# 16bit_Banked_Switches.net
KiCad netlist of a schematic drawn in EAGLE
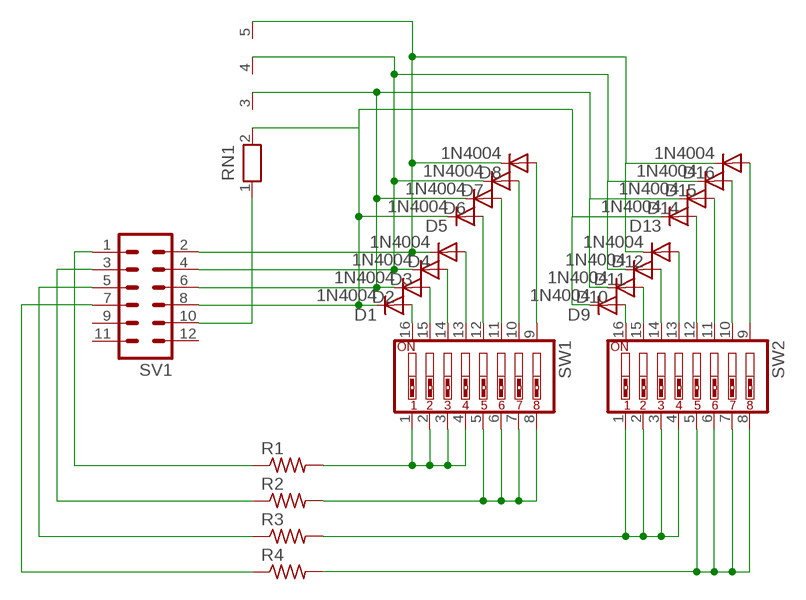
[diagram p0: schematic, sheet 1]

(export (version "E")
  (design (tool "Eeschema 10.0.6"))
  (components
    (comp (ref "D1")
      (value "1N4004")
      (footprint "eagle-import:DO41-10")
      (libsource (lib "eagle-import") (part "1N4004"))
    )
    (comp (ref "D2")
      (value "1N4004")
      (footprint "eagle-import:DO41-10")
      (libsource (lib "eagle-import") (part "1N4004"))
    )
    (comp (ref "D3")
      (value "1N4004")
      (footprint "eagle-import:DO41-10")
      (libsource (lib "eagle-import") (part "1N4004"))
    )
    (comp (ref "D4")
      (value "1N4004")
      (footprint "eagle-import:DO41-10")
      (libsource (lib "eagle-import") (part "1N4004"))
    )
    (comp (ref "D5")
      (value "1N4004")
      (footprint "eagle-import:DO41-10")
      (libsource (lib "eagle-import") (part "1N4004"))
    )
    (comp (ref "D6")
      (value "1N4004")
      (footprint "eagle-import:DO41-10")
      (libsource (lib "eagle-import") (part "1N4004"))
    )
    (comp (ref "D7")
      (value "1N4004")
      (footprint "eagle-import:DO41-10")
      (libsource (lib "eagle-import") (part "1N4004"))
    )
    (comp (ref "D8")
      (value "1N4004")
      (footprint "eagle-import:DO41-10")
      (libsource (lib "eagle-import") (part "1N4004"))
    )
    (comp (ref "D9")
      (value "1N4004")
      (footprint "eagle-import:DO41-10")
      (libsource (lib "eagle-import") (part "1N4004"))
    )
    (comp (ref "D10")
      (value "1N4004")
      (footprint "eagle-import:DO41-10")
      (libsource (lib "eagle-import") (part "1N4004"))
    )
    (comp (ref "D11")
      (value "1N4004")
      (footprint "eagle-import:DO41-10")
      (libsource (lib "eagle-import") (part "1N4004"))
    )
    (comp (ref "D12")
      (value "1N4004")
      (footprint "eagle-import:DO41-10")
      (libsource (lib "eagle-import") (part "1N4004"))
    )
    (comp (ref "D13")
      (value "1N4004")
      (footprint "eagle-import:DO41-10")
      (libsource (lib "eagle-import") (part "1N4004"))
    )
    (comp (ref "D14")
      (value "1N4004")
      (footprint "eagle-import:DO41-10")
      (libsource (lib "eagle-import") (part "1N4004"))
    )
    (comp (ref "D15")
      (value "1N4004")
      (footprint "eagle-import:DO41-10")
      (libsource (lib "eagle-import") (part "1N4004"))
    )
    (comp (ref "D16")
      (value "1N4004")
      (footprint "eagle-import:DO41-10")
      (libsource (lib "eagle-import") (part "1N4004"))
    )
    (comp (ref "R1")
      (value "R-US_0207/9")
      (footprint "eagle-import:0207_9")
      (libsource (lib "eagle-import") (part "R-US_0207/9"))
    )
    (comp (ref "R2")
      (value "R-US_0207/9")
      (footprint "eagle-import:0207_9")
      (libsource (lib "eagle-import") (part "R-US_0207/9"))
    )
    (comp (ref "R3")
      (value "R-US_0207/9")
      (footprint "eagle-import:0207_9")
      (libsource (lib "eagle-import") (part "R-US_0207/9"))
    )
    (comp (ref "R4")
      (value "R-US_0207/9")
      (footprint "eagle-import:0207_9")
      (libsource (lib "eagle-import") (part "R-US_0207/9"))
    )
    (comp (ref "RN1")
      (value "RN04")
      (footprint "eagle-import:RN-5")
      (libsource (lib "eagle-import") (part "RN04"))
    )
    (comp (ref "SV1")
      (value "MA06-2")
      (footprint "eagle-import:MA06-2")
      (libsource (lib "eagle-import") (part "MA06-2"))
    )
    (comp (ref "SW1")
      (value "SW_DIP-8")
      (footprint "eagle-import:EDG-08")
      (libsource (lib "eagle-import") (part "SW_DIP-8"))
    )
    (comp (ref "SW2")
      (value "SW_DIP-8")
      (footprint "eagle-import:EDG-08")
      (libsource (lib "eagle-import") (part "SW_DIP-8"))
    )
  )
  (nets
    (net (code "1") (name "Net-(D1-PadA)") (class "Default")
      (node (ref "D1") (pin "A") (pinfunction "A_A") (pintype "passive"))
      (node (ref "SW1") (pin "16") (pinfunction "16_16") (pintype "passive"))
    )
    (net (code "2") (name "Net-(D1-PadC)") (class "Default")
      (node (ref "D1") (pin "C") (pinfunction "C_C") (pintype "passive"))
      (node (ref "D13") (pin "C") (pinfunction "C_C") (pintype "passive"))
      (node (ref "D5") (pin "C") (pinfunction "C_C") (pintype "passive"))
      (node (ref "D9") (pin "C") (pinfunction "C_C") (pintype "passive"))
      (node (ref "RN1") (pin "2") (pinfunction "2_2") (pintype "passive"))
      (node (ref "SV1") (pin "8") (pinfunction "8_8") (pintype "passive"))
    )
    (net (code "3") (name "Net-(D2-PadA)") (class "Default")
      (node (ref "D2") (pin "A") (pinfunction "A_A") (pintype "passive"))
      (node (ref "SW1") (pin "15") (pinfunction "15_15") (pintype "passive"))
    )
    (net (code "4") (name "Net-(D3-PadA)") (class "Default")
      (node (ref "D3") (pin "A") (pinfunction "A_A") (pintype "passive"))
      (node (ref "SW1") (pin "14") (pinfunction "14_14") (pintype "passive"))
    )
    (net (code "5") (name "Net-(D4-PadA)") (class "Default")
      (node (ref "D4") (pin "A") (pinfunction "A_A") (pintype "passive"))
      (node (ref "SW1") (pin "13") (pinfunction "13_13") (pintype "passive"))
    )
    (net (code "6") (name "Net-(D5-PadA)") (class "Default")
      (node (ref "D5") (pin "A") (pinfunction "A_A") (pintype "passive"))
      (node (ref "SW1") (pin "12") (pinfunction "12_12") (pintype "passive"))
    )
    (net (code "7") (name "Net-(D6-PadA)") (class "Default")
      (node (ref "D6") (pin "A") (pinfunction "A_A") (pintype "passive"))
      (node (ref "SW1") (pin "11") (pinfunction "11_11") (pintype "passive"))
    )
    (net (code "8") (name "Net-(D7-PadA)") (class "Default")
      (node (ref "D7") (pin "A") (pinfunction "A_A") (pintype "passive"))
      (node (ref "SW1") (pin "10") (pinfunction "10_10") (pintype "passive"))
    )
    (net (code "9") (name "Net-(D8-PadA)") (class "Default")
      (node (ref "D8") (pin "A") (pinfunction "A_A") (pintype "passive"))
      (node (ref "SW1") (pin "9") (pinfunction "9_9") (pintype "passive"))
    )
    (net (code "10") (name "Net-(D9-PadA)") (class "Default")
      (node (ref "D9") (pin "A") (pinfunction "A_A") (pintype "passive"))
      (node (ref "SW2") (pin "16") (pinfunction "16_16") (pintype "passive"))
    )
    (net (code "11") (name "Net-(D10-PadA)") (class "Default")
      (node (ref "D10") (pin "A") (pinfunction "A_A") (pintype "passive"))
      (node (ref "SW2") (pin "15") (pinfunction "15_15") (pintype "passive"))
    )
    (net (code "12") (name "Net-(D10-PadC)") (class "Default")
      (node (ref "D10") (pin "C") (pinfunction "C_C") (pintype "passive"))
      (node (ref "D14") (pin "C") (pinfunction "C_C") (pintype "passive"))
      (node (ref "D2") (pin "C") (pinfunction "C_C") (pintype "passive"))
      (node (ref "D6") (pin "C") (pinfunction "C_C") (pintype "passive"))
      (node (ref "RN1") (pin "3") (pinfunction "3_3") (pintype "passive"))
      (node (ref "SV1") (pin "6") (pinfunction "6_6") (pintype "passive"))
    )
    (net (code "13") (name "Net-(D11-PadA)") (class "Default")
      (node (ref "D11") (pin "A") (pinfunction "A_A") (pintype "passive"))
      (node (ref "SW2") (pin "14") (pinfunction "14_14") (pintype "passive"))
    )
    (net (code "14") (name "Net-(D11-PadC)") (class "Default")
      (node (ref "D11") (pin "C") (pinfunction "C_C") (pintype "passive"))
      (node (ref "D15") (pin "C") (pinfunction "C_C") (pintype "passive"))
      (node (ref "D3") (pin "C") (pinfunction "C_C") (pintype "passive"))
      (node (ref "D7") (pin "C") (pinfunction "C_C") (pintype "passive"))
      (node (ref "RN1") (pin "4") (pinfunction "4_4") (pintype "passive"))
      (node (ref "SV1") (pin "4") (pinfunction "4_4") (pintype "passive"))
    )
    (net (code "15") (name "Net-(D12-PadA)") (class "Default")
      (node (ref "D12") (pin "A") (pinfunction "A_A") (pintype "passive"))
      (node (ref "SW2") (pin "13") (pinfunction "13_13") (pintype "passive"))
    )
    (net (code "16") (name "Net-(D12-PadC)") (class "Default")
      (node (ref "D12") (pin "C") (pinfunction "C_C") (pintype "passive"))
      (node (ref "D16") (pin "C") (pinfunction "C_C") (pintype "passive"))
      (node (ref "D4") (pin "C") (pinfunction "C_C") (pintype "passive"))
      (node (ref "D8") (pin "C") (pinfunction "C_C") (pintype "passive"))
      (node (ref "RN1") (pin "5") (pinfunction "5_5") (pintype "passive"))
      (node (ref "SV1") (pin "2") (pinfunction "2_2") (pintype "passive"))
    )
    (net (code "17") (name "Net-(D13-PadA)") (class "Default")
      (node (ref "D13") (pin "A") (pinfunction "A_A") (pintype "passive"))
      (node (ref "SW2") (pin "12") (pinfunction "12_12") (pintype "passive"))
    )
    (net (code "18") (name "Net-(D14-PadA)") (class "Default")
      (node (ref "D14") (pin "A") (pinfunction "A_A") (pintype "passive"))
      (node (ref "SW2") (pin "11") (pinfunction "11_11") (pintype "passive"))
    )
    (net (code "19") (name "Net-(D15-PadA)") (class "Default")
      (node (ref "D15") (pin "A") (pinfunction "A_A") (pintype "passive"))
      (node (ref "SW2") (pin "10") (pinfunction "10_10") (pintype "passive"))
    )
    (net (code "20") (name "Net-(D16-PadA)") (class "Default")
      (node (ref "D16") (pin "A") (pinfunction "A_A") (pintype "passive"))
      (node (ref "SW2") (pin "9") (pinfunction "9_9") (pintype "passive"))
    )
    (net (code "21") (name "Net-(R1-Pad1)") (class "Default")
      (node (ref "R1") (pin "1") (pinfunction "1_1") (pintype "passive"))
      (node (ref "SV1") (pin "1") (pinfunction "1_1") (pintype "passive"))
    )
    (net (code "22") (name "Net-(R1-Pad2)") (class "Default")
      (node (ref "R1") (pin "2") (pinfunction "2_2") (pintype "passive"))
      (node (ref "SW1") (pin "1") (pinfunction "1_1") (pintype "passive"))
      (node (ref "SW1") (pin "2") (pinfunction "2_2") (pintype "passive"))
      (node (ref "SW1") (pin "3") (pinfunction "3_3") (pintype "passive"))
      (node (ref "SW1") (pin "4") (pinfunction "4_4") (pintype "passive"))
    )
    (net (code "23") (name "Net-(R2-Pad1)") (class "Default")
      (node (ref "R2") (pin "1") (pinfunction "1_1") (pintype "passive"))
      (node (ref "SV1") (pin "3") (pinfunction "3_3") (pintype "passive"))
    )
    (net (code "24") (name "Net-(R2-Pad2)") (class "Default")
      (node (ref "R2") (pin "2") (pinfunction "2_2") (pintype "passive"))
      (node (ref "SW1") (pin "5") (pinfunction "5_5") (pintype "passive"))
      (node (ref "SW1") (pin "6") (pinfunction "6_6") (pintype "passive"))
      (node (ref "SW1") (pin "7") (pinfunction "7_7") (pintype "passive"))
      (node (ref "SW1") (pin "8") (pinfunction "8_8") (pintype "passive"))
    )
    (net (code "25") (name "Net-(R3-Pad1)") (class "Default")
      (node (ref "R3") (pin "1") (pinfunction "1_1") (pintype "passive"))
      (node (ref "SV1") (pin "5") (pinfunction "5_5") (pintype "passive"))
    )
    (net (code "26") (name "Net-(R3-Pad2)") (class "Default")
      (node (ref "R3") (pin "2") (pinfunction "2_2") (pintype "passive"))
      (node (ref "SW2") (pin "1") (pinfunction "1_1") (pintype "passive"))
      (node (ref "SW2") (pin "2") (pinfunction "2_2") (pintype "passive"))
      (node (ref "SW2") (pin "3") (pinfunction "3_3") (pintype "passive"))
      (node (ref "SW2") (pin "4") (pinfunction "4_4") (pintype "passive"))
    )
    (net (code "27") (name "Net-(R4-Pad1)") (class "Default")
      (node (ref "R4") (pin "1") (pinfunction "1_1") (pintype "passive"))
      (node (ref "SV1") (pin "7") (pinfunction "7_7") (pintype "passive"))
    )
    (net (code "28") (name "Net-(R4-Pad2)") (class "Default")
      (node (ref "R4") (pin "2") (pinfunction "2_2") (pintype "passive"))
      (node (ref "SW2") (pin "5") (pinfunction "5_5") (pintype "passive"))
      (node (ref "SW2") (pin "6") (pinfunction "6_6") (pintype "passive"))
      (node (ref "SW2") (pin "7") (pinfunction "7_7") (pintype "passive"))
      (node (ref "SW2") (pin "8") (pinfunction "8_8") (pintype "passive"))
    )
    (net (code "29") (name "Net-(RN1-Pad1)") (class "Default")
      (node (ref "RN1") (pin "1") (pinfunction "1_1") (pintype "passive"))
      (node (ref "SV1") (pin "10") (pinfunction "10_10") (pintype "passive"))
    )
    (net (code "30") (name "unconnected-(SV1-Pad9)") (class "Default")
      (node (ref "SV1") (pin "9") (pinfunction "9_9") (pintype "passive"))
    )
    (net (code "31") (name "unconnected-(SV1-Pad11)") (class "Default")
      (node (ref "SV1") (pin "11") (pinfunction "11_11") (pintype "passive"))
    )
    (net (code "32") (name "unconnected-(SV1-Pad12)") (class "Default")
      (node (ref "SV1") (pin "12") (pinfunction "12_12") (pintype "passive"))
    )
  )
)
